# Teensy-Maxuino-Slave.net
KiCad netlist of a schematic drawn in EAGLE
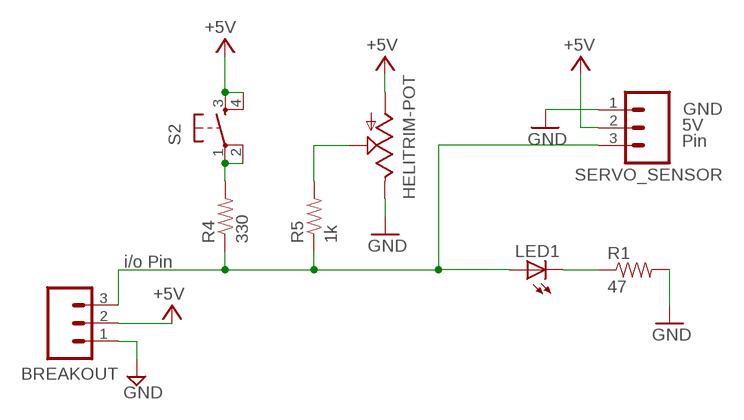
[diagram p0: schematic, sheet 1]

(export (version "E")
  (design (tool "Eeschema 10.0.6"))
  (components
    (comp (ref "BREAKOUT")
      (value "M03PTH")
      (footprint "eagle-import:1X03")
      (fields (field (name "IOPIN") "i/o Pin"))
      (libsource (lib "eagle-import") (part "SparkFun-Connectors_M03PTH"))
    )
    (comp (ref "LED1")
      (value "LED3MM")
      (footprint "eagle-import:LED3MM")
      (libsource (lib "eagle-import") (part "LED3MM"))
    )
    (comp (ref "R1")
      (value "47")
      (footprint "eagle-import:1_6W-RES")
      (libsource (lib "eagle-import") (part "RESISTORPTH-1/6W"))
    )
    (comp (ref "R4")
      (value "330")
      (footprint "eagle-import:1_6W-RES")
      (libsource (lib "eagle-import") (part "RESISTORPTH-1/6W"))
    )
    (comp (ref "R5")
      (value "1k")
      (footprint "eagle-import:1_6W-RES")
      (libsource (lib "eagle-import") (part "RESISTORPTH-1/6W"))
    )
    (comp (ref "S2")
      (value "TAC_SWITCHPTH")
      (footprint "eagle-import:TACTILE-PTH")
      (libsource (lib "eagle-import") (part "TAC_SWITCHPTH"))
    )
    (comp (ref "SERVO_SENSOR")
      (value "M03PTH")
      (footprint "eagle-import:1X03")
      (fields (field (name "5V") "5V") (field (name "PIN") "Pin"))
      (libsource (lib "eagle-import") (part "M03PTH"))
    )
    (comp (ref "U$1")
      (value "HELITRIM-POT")
      (footprint "eagle-import:HELITRIM-POT")
      (libsource (lib "eagle-import") (part "HELITRIM-POT"))
    )
  )
  (nets
    (net (code "1") (name "+5V") (class "Default")
      (node (ref "BREAKOUT") (pin "2") (pinfunction "2_2") (pintype "passive"))
      (node (ref "S2") (pin "3") (pinfunction "3_3") (pintype "passive"))
      (node (ref "S2") (pin "4") (pinfunction "4_4") (pintype "passive"))
      (node (ref "SERVO_SENSOR") (pin "2") (pinfunction "2_2") (pintype "passive"))
      (node (ref "U$1") (pin "P$1") (pinfunction "A_P$1") (pintype "passive"))
    )
    (net (code "2") (name "GND") (class "Default")
      (node (ref "BREAKOUT") (pin "1") (pinfunction "1_1") (pintype "passive"))
      (node (ref "R1") (pin "2") (pinfunction "2_2") (pintype "passive"))
      (node (ref "SERVO_SENSOR") (pin "1") (pinfunction "1_1") (pintype "passive"))
      (node (ref "U$1") (pin "P$2") (pinfunction "E_P$2") (pintype "passive"))
    )
    (net (code "3") (name "Net-(BREAKOUT-Pad3)") (class "Default")
      (node (ref "BREAKOUT") (pin "3") (pinfunction "3_3") (pintype "passive"))
      (node (ref "LED1") (pin "A") (pinfunction "A_A") (pintype "passive"))
      (node (ref "R4") (pin "1") (pinfunction "1_1") (pintype "passive"))
      (node (ref "R5") (pin "1") (pinfunction "1_1") (pintype "passive"))
      (node (ref "SERVO_SENSOR") (pin "3") (pinfunction "3_3") (pintype "passive"))
    )
    (net (code "4") (name "Net-(LED1-C)") (class "Default")
      (node (ref "LED1") (pin "K") (pinfunction "C_K") (pintype "passive"))
      (node (ref "R1") (pin "1") (pinfunction "1_1") (pintype "passive"))
    )
    (net (code "5") (name "Net-(R4-Pad2)") (class "Default")
      (node (ref "R4") (pin "2") (pinfunction "2_2") (pintype "passive"))
      (node (ref "S2") (pin "1") (pinfunction "1_1") (pintype "passive"))
      (node (ref "S2") (pin "2") (pinfunction "2_2") (pintype "passive"))
    )
    (net (code "6") (name "Net-(U$1B-S)") (class "Default")
      (node (ref "R5") (pin "2") (pinfunction "2_2") (pintype "passive"))
      (node (ref "U$1") (pin "P$3") (pinfunction "S_P$3") (pintype "passive"))
    )
  )
)
